# v1.net
KiCad netlist of a schematic drawn in EAGLE
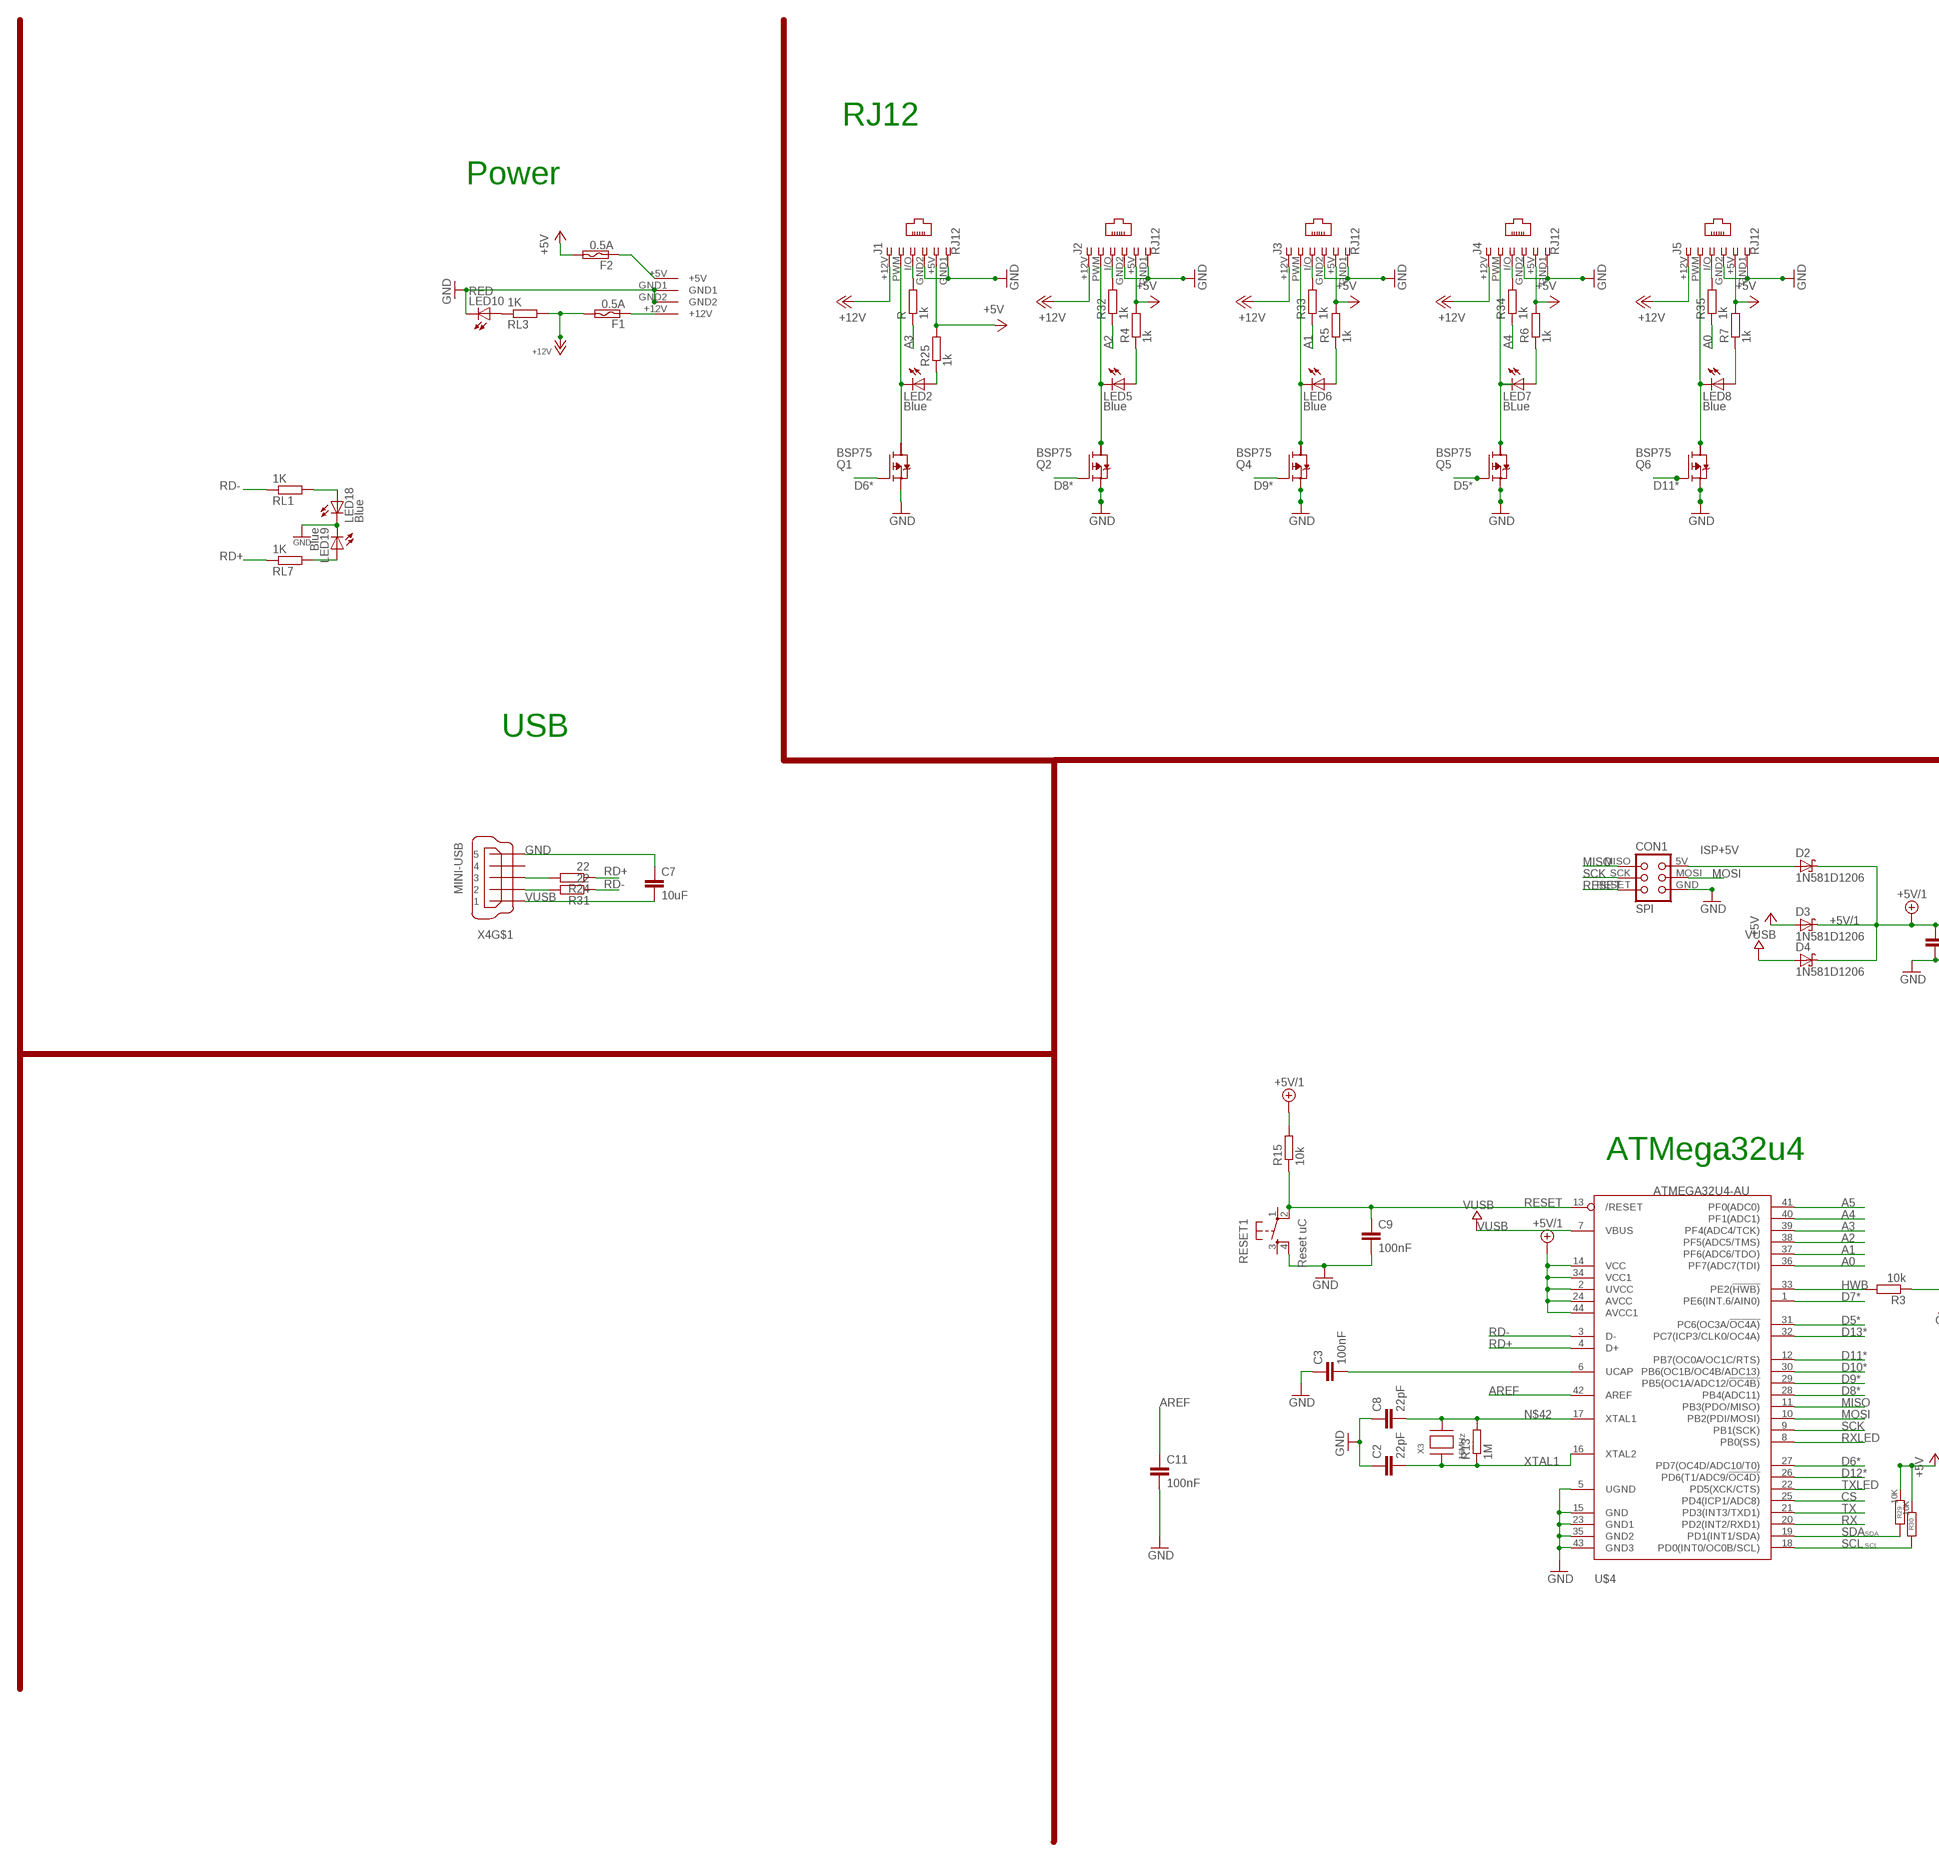
[diagram p0: schematic, sheet 1, part 1 of 2]
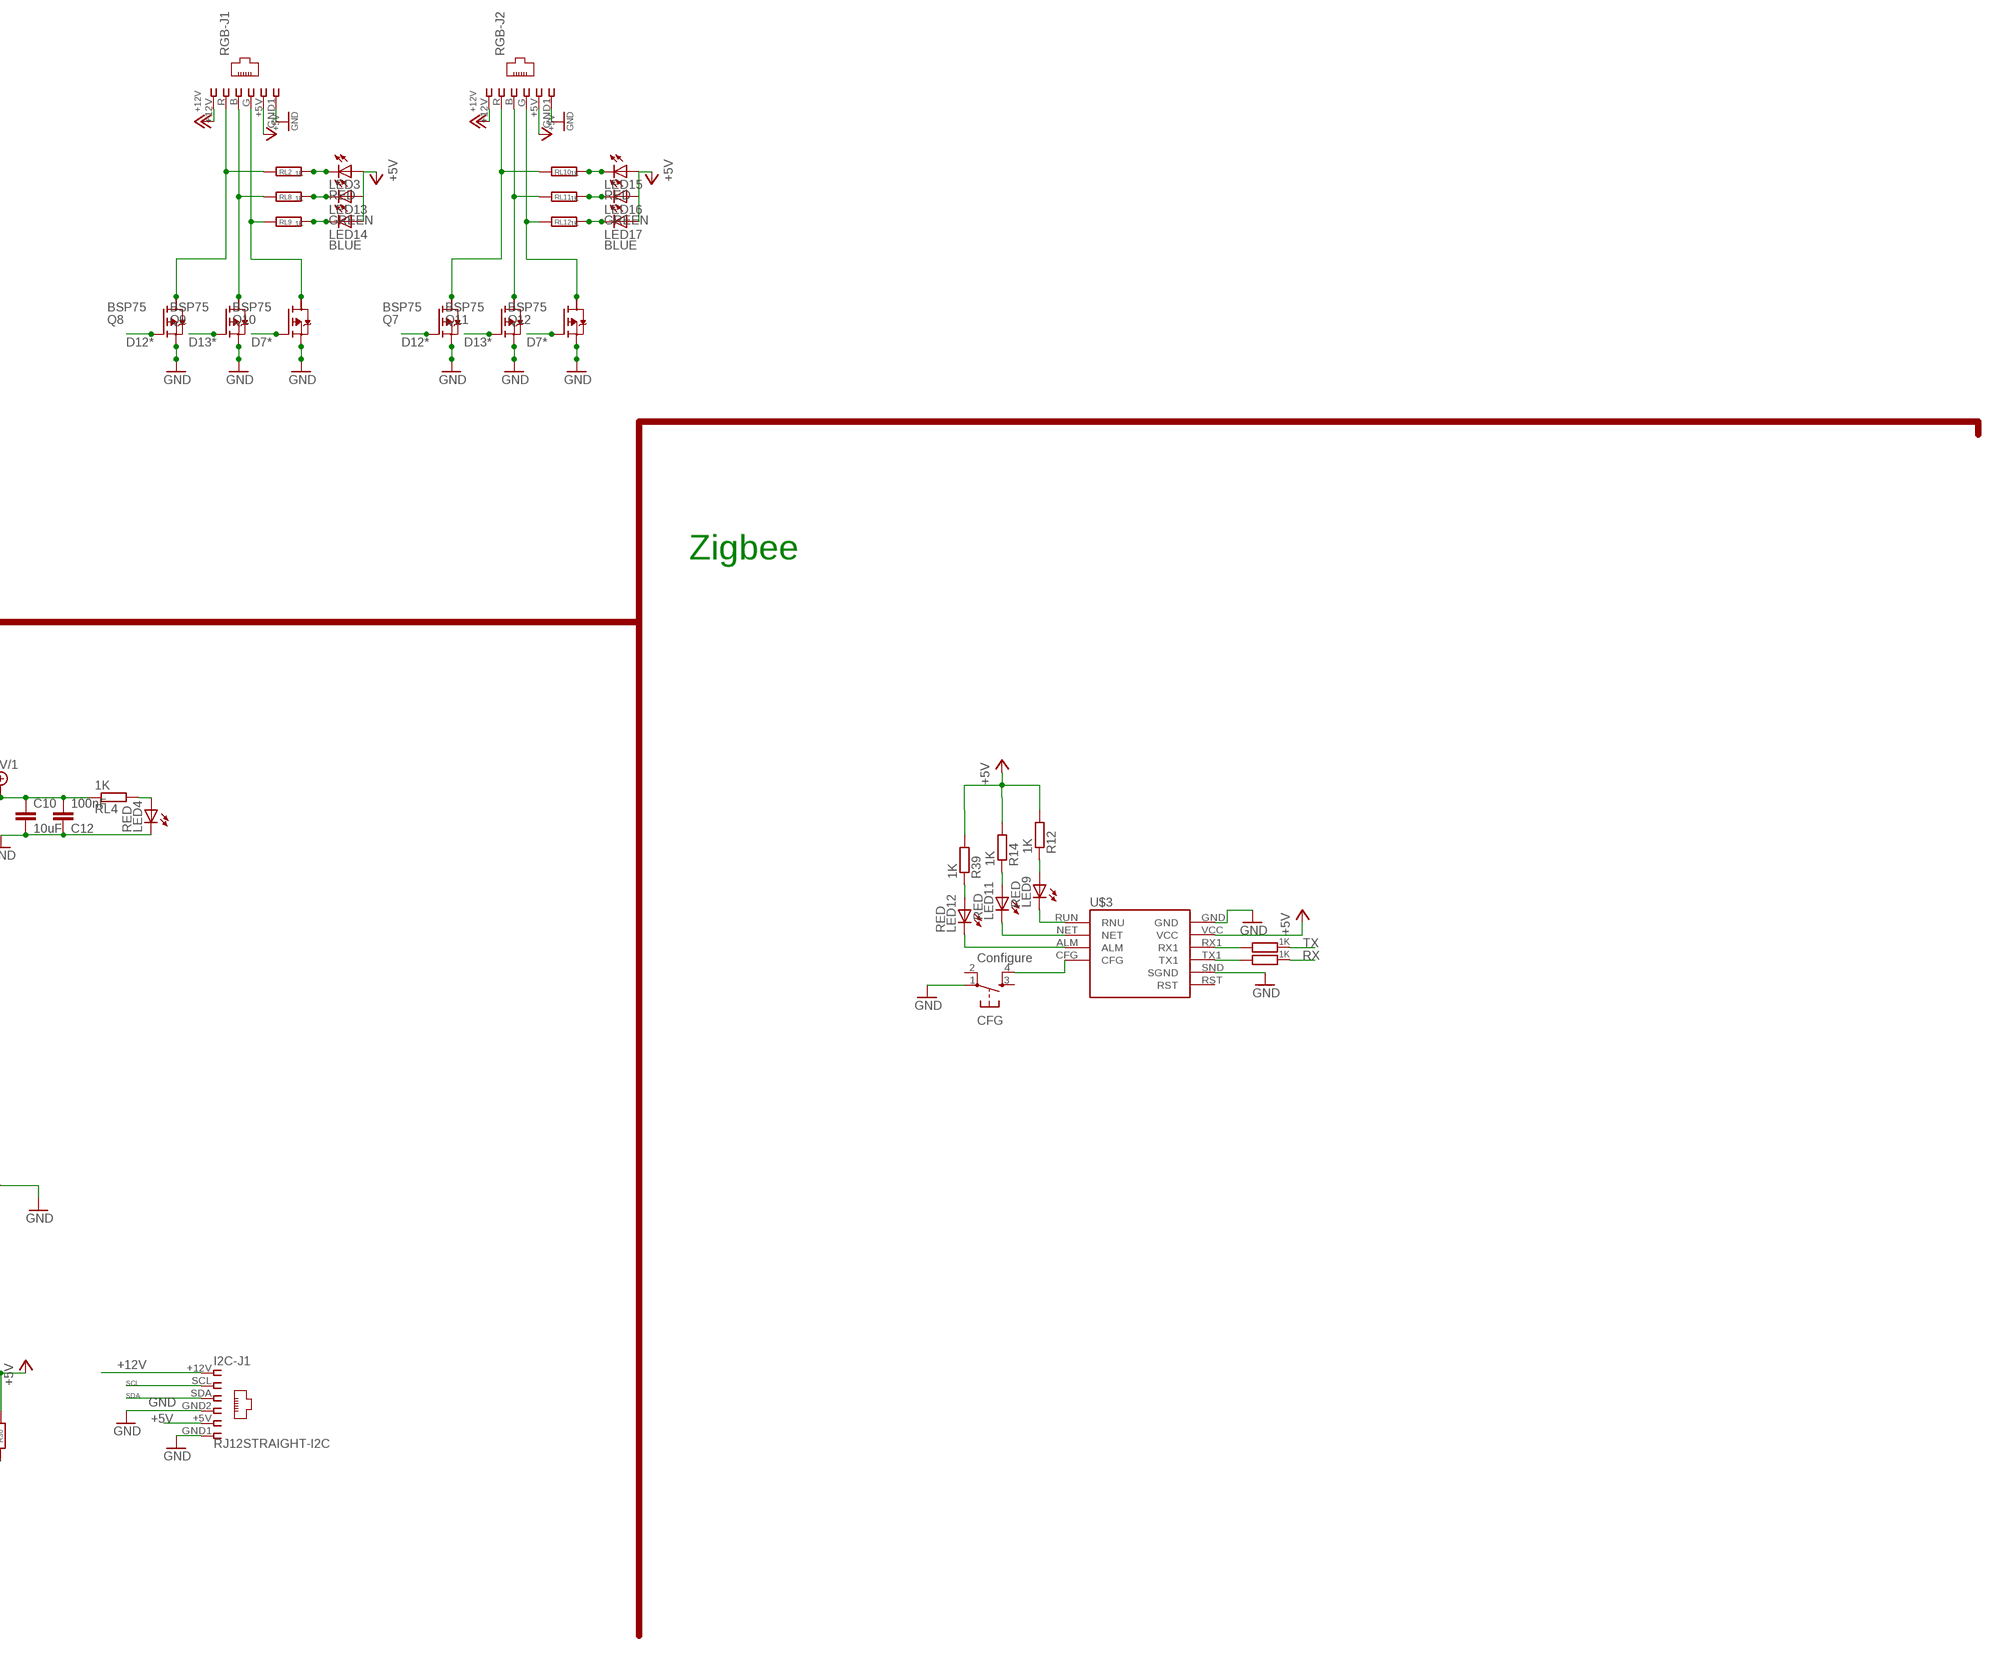
[diagram p1: schematic, sheet 1, part 2 of 2]

(export (version "E")
  (design (tool "Eeschema 10.0.6"))
  (components
    (comp (ref "C2")
      (value "22pF")
      (footprint "eagle-import:C1206")
      (libsource (lib "eagle-import") (part "C-EUC1206"))
    )
    (comp (ref "C3")
      (value "100nF")
      (footprint "eagle-import:C1206")
      (libsource (lib "eagle-import") (part "C-EUC1206"))
    )
    (comp (ref "C7")
      (value "10uF")
      (footprint "eagle-import:C1206")
      (libsource (lib "eagle-import") (part "C-EUC1206"))
    )
    (comp (ref "C8")
      (value "22pF")
      (footprint "eagle-import:C1206")
      (libsource (lib "eagle-import") (part "C-EUC1206"))
    )
    (comp (ref "C9")
      (value "100nF")
      (footprint "eagle-import:C1206")
      (libsource (lib "eagle-import") (part "C-EUC1206"))
    )
    (comp (ref "C10")
      (value "10uF")
      (footprint "eagle-import:C1206")
      (libsource (lib "eagle-import") (part "C-EUC1206"))
    )
    (comp (ref "C11")
      (value "100nF")
      (footprint "eagle-import:C1206")
      (libsource (lib "eagle-import") (part "C-EUC1206"))
    )
    (comp (ref "C12")
      (value "100nF")
      (footprint "eagle-import:C1206")
      (libsource (lib "eagle-import") (part "C-EUC1206"))
    )
    (comp (ref "CFG")
      (value "Configure")
      (footprint "eagle-import:TACTILE_SWITCH_SMD")
      (libsource (lib "eagle-import") (part "TAC_SWITCHSMD"))
    )
    (comp (ref "CON1")
      (value "SPI")
      (footprint "eagle-import:TC2030-MCP-NL")
      (libsource (lib "eagle-import") (part "TINYISPT"))
    )
    (comp (ref "D2")
      (value "1N581D1206")
      (footprint "eagle-import:LED-1206")
      (libsource (lib "eagle-import") (part "1N581D1206"))
    )
    (comp (ref "D3")
      (value "1N581D1206")
      (footprint "eagle-import:LED-1206")
      (libsource (lib "eagle-import") (part "1N581D1206"))
    )
    (comp (ref "D4")
      (value "1N581D1206")
      (footprint "eagle-import:LED-1206")
      (libsource (lib "eagle-import") (part "1N581D1206"))
    )
    (comp (ref "F1")
      (value "0.5A")
      (footprint "eagle-import:C1812")
      (libsource (lib "eagle-import") (part "POLYSWITCHSMD1812"))
    )
    (comp (ref "F2")
      (value "0.5A")
      (footprint "eagle-import:C1812")
      (libsource (lib "eagle-import") (part "POLYSWITCHSMD1812"))
    )
    (comp (ref "I2C-J1")
      (value "RJ12STRAIGHT-I2C")
      (footprint "eagle-import:RJ12-STRAIGHT-I2C")
      (libsource (lib "eagle-import") (part "RJ12STRAIGHT-I2C"))
    )
    (comp (ref "J1")
      (value "RJ12")
      (footprint "eagle-import:RJ12-STRAIGHT")
      (libsource (lib "eagle-import") (part "RJ12STRAIGHT"))
    )
    (comp (ref "J2")
      (value "RJ12")
      (footprint "eagle-import:RJ12-STRAIGHT")
      (libsource (lib "eagle-import") (part "RJ12STRAIGHT"))
    )
    (comp (ref "J3")
      (value "RJ12")
      (footprint "eagle-import:RJ12-STRAIGHT")
      (libsource (lib "eagle-import") (part "RJ12STRAIGHT"))
    )
    (comp (ref "J4")
      (value "RJ12")
      (footprint "eagle-import:RJ12-STRAIGHT")
      (libsource (lib "eagle-import") (part "RJ12STRAIGHT"))
    )
    (comp (ref "J5")
      (value "RJ12")
      (footprint "eagle-import:RJ12-STRAIGHT")
      (libsource (lib "eagle-import") (part "RJ12STRAIGHT"))
    )
    (comp (ref "LED2")
      (value "Blue")
      (footprint "eagle-import:CHIPLED_1206")
      (libsource (lib "eagle-import") (part "LEDCHIPLED_1206"))
    )
    (comp (ref "LED3")
      (value "RED")
      (footprint "eagle-import:CHIPLED_1206")
      (libsource (lib "eagle-import") (part "LEDCHIPLED_1206"))
    )
    (comp (ref "LED4")
      (value "RED")
      (footprint "eagle-import:CHIPLED_1206")
      (libsource (lib "eagle-import") (part "LEDCHIPLED_1206"))
    )
    (comp (ref "LED5")
      (value "Blue")
      (footprint "eagle-import:CHIPLED_1206")
      (libsource (lib "eagle-import") (part "LEDCHIPLED_1206"))
    )
    (comp (ref "LED6")
      (value "Blue")
      (footprint "eagle-import:CHIPLED_1206")
      (libsource (lib "eagle-import") (part "LEDCHIPLED_1206"))
    )
    (comp (ref "LED7")
      (value "BLue")
      (footprint "eagle-import:CHIPLED_1206")
      (libsource (lib "eagle-import") (part "LEDCHIPLED_1206"))
    )
    (comp (ref "LED8")
      (value "Blue")
      (footprint "eagle-import:CHIPLED_1206")
      (libsource (lib "eagle-import") (part "LEDCHIPLED_1206"))
    )
    (comp (ref "LED9")
      (value "RED")
      (footprint "eagle-import:CHIP-LED0805")
      (libsource (lib "eagle-import") (part "LEDCHIP-LED0805"))
    )
    (comp (ref "LED10")
      (value "RED")
      (footprint "eagle-import:CHIPLED_1206")
      (libsource (lib "eagle-import") (part "LEDCHIPLED_1206"))
    )
    (comp (ref "LED11")
      (value "RED")
      (footprint "eagle-import:CHIP-LED0805")
      (libsource (lib "eagle-import") (part "LEDCHIP-LED0805"))
    )
    (comp (ref "LED12")
      (value "RED")
      (footprint "eagle-import:CHIP-LED0805")
      (libsource (lib "eagle-import") (part "LEDCHIP-LED0805"))
    )
    (comp (ref "LED13")
      (value "GREEN")
      (footprint "eagle-import:CHIPLED_1206")
      (libsource (lib "eagle-import") (part "LEDCHIPLED_1206"))
    )
    (comp (ref "LED14")
      (value "BLUE")
      (footprint "eagle-import:CHIPLED_1206")
      (libsource (lib "eagle-import") (part "LEDCHIPLED_1206"))
    )
    (comp (ref "LED15")
      (value "RED")
      (footprint "eagle-import:CHIPLED_1206")
      (libsource (lib "eagle-import") (part "LEDCHIPLED_1206"))
    )
    (comp (ref "LED16")
      (value "GREEN")
      (footprint "eagle-import:CHIPLED_1206")
      (libsource (lib "eagle-import") (part "LEDCHIPLED_1206"))
    )
    (comp (ref "LED17")
      (value "BLUE")
      (footprint "eagle-import:CHIPLED_1206")
      (libsource (lib "eagle-import") (part "LEDCHIPLED_1206"))
    )
    (comp (ref "LED18")
      (value "Blue")
      (footprint "eagle-import:CHIPLED_1206")
      (libsource (lib "eagle-import") (part "LEDCHIPLED_1206"))
    )
    (comp (ref "LED19")
      (value "Blue")
      (footprint "eagle-import:CHIPLED_1206")
      (libsource (lib "eagle-import") (part "LEDCHIPLED_1206"))
    )
    (comp (ref "Q1")
      (value "BSP75")
      (footprint "eagle-import:PG-SOT-223")
      (libsource (lib "eagle-import") (part "BSP613P"))
    )
    (comp (ref "Q2")
      (value "BSP75")
      (footprint "eagle-import:PG-SOT-223")
      (libsource (lib "eagle-import") (part "BSP613P"))
    )
    (comp (ref "Q4")
      (value "BSP75")
      (footprint "eagle-import:PG-SOT-223")
      (libsource (lib "eagle-import") (part "BSP613P"))
    )
    (comp (ref "Q5")
      (value "BSP75")
      (footprint "eagle-import:PG-SOT-223")
      (libsource (lib "eagle-import") (part "BSP613P"))
    )
    (comp (ref "Q6")
      (value "BSP75")
      (footprint "eagle-import:PG-SOT-223")
      (libsource (lib "eagle-import") (part "BSP613P"))
    )
    (comp (ref "Q7")
      (value "BSP75")
      (footprint "eagle-import:PG-SOT-223")
      (libsource (lib "eagle-import") (part "BSP613P"))
    )
    (comp (ref "Q8")
      (value "BSP75")
      (footprint "eagle-import:PG-SOT-223")
      (libsource (lib "eagle-import") (part "BSP613P"))
    )
    (comp (ref "Q9")
      (value "BSP75")
      (footprint "eagle-import:PG-SOT-223")
      (libsource (lib "eagle-import") (part "BSP613P"))
    )
    (comp (ref "Q10")
      (value "BSP75")
      (footprint "eagle-import:PG-SOT-223")
      (libsource (lib "eagle-import") (part "BSP613P"))
    )
    (comp (ref "Q11")
      (value "BSP75")
      (footprint "eagle-import:PG-SOT-223")
      (libsource (lib "eagle-import") (part "BSP613P"))
    )
    (comp (ref "Q12")
      (value "BSP75")
      (footprint "eagle-import:PG-SOT-223")
      (libsource (lib "eagle-import") (part "BSP613P"))
    )
    (comp (ref "R")
      (value "1k")
      (footprint "eagle-import:R0805")
      (libsource (lib "eagle-import") (part "R-EU_R0805"))
    )
    (comp (ref "R3")
      (value "10k")
      (footprint "eagle-import:M0805")
      (libsource (lib "eagle-import") (part "resistor_R-EU_M0805"))
    )
    (comp (ref "R4")
      (value "1k")
      (footprint "eagle-import:R0805")
      (libsource (lib "eagle-import") (part "R-EU_R0805"))
    )
    (comp (ref "R5")
      (value "1k")
      (footprint "eagle-import:R0805")
      (libsource (lib "eagle-import") (part "R-EU_R0805"))
    )
    (comp (ref "R6")
      (value "1k")
      (footprint "eagle-import:R0805")
      (libsource (lib "eagle-import") (part "R-EU_R0805"))
    )
    (comp (ref "R7")
      (value "1k")
      (footprint "eagle-import:R0805")
      (libsource (lib "eagle-import") (part "R-EU_R0805"))
    )
    (comp (ref "R8")
      (value "1K")
      (footprint "eagle-import:R0805")
      (libsource (lib "eagle-import") (part "R-EU_R0805"))
    )
    (comp (ref "R11")
      (value "1K")
      (footprint "eagle-import:R0805")
      (libsource (lib "eagle-import") (part "R-EU_R0805"))
    )
    (comp (ref "R12")
      (value "1K")
      (footprint "eagle-import:R0805")
      (libsource (lib "eagle-import") (part "R-EU_R0805"))
    )
    (comp (ref "R13")
      (value "1M")
      (footprint "eagle-import:R1206")
      (libsource (lib "eagle-import") (part "R-EU_R1206"))
    )
    (comp (ref "R14")
      (value "1K")
      (footprint "eagle-import:R0805")
      (libsource (lib "eagle-import") (part "R-EU_R0805"))
    )
    (comp (ref "R15")
      (value "10k")
      (footprint "eagle-import:M0805")
      (libsource (lib "eagle-import") (part "resistor_R-EU_M0805"))
    )
    (comp (ref "R24")
      (value "22")
      (footprint "eagle-import:M1206")
      (libsource (lib "eagle-import") (part "resistor_R-EU_M1206"))
    )
    (comp (ref "R25")
      (value "1k")
      (footprint "eagle-import:R0805")
      (libsource (lib "eagle-import") (part "R-EU_R0805"))
    )
    (comp (ref "R29")
      (value "10K")
      (footprint "eagle-import:M0805")
      (libsource (lib "eagle-import") (part "resistor_R-EU_M0805"))
    )
    (comp (ref "R30")
      (value "10K")
      (footprint "eagle-import:M0805")
      (libsource (lib "eagle-import") (part "resistor_R-EU_M0805"))
    )
    (comp (ref "R31")
      (value "22")
      (footprint "eagle-import:M1206")
      (libsource (lib "eagle-import") (part "resistor_R-EU_M1206"))
    )
    (comp (ref "R32")
      (value "1k")
      (footprint "eagle-import:R0805")
      (libsource (lib "eagle-import") (part "R-EU_R0805"))
    )
    (comp (ref "R33")
      (value "1k")
      (footprint "eagle-import:R0805")
      (libsource (lib "eagle-import") (part "R-EU_R0805"))
    )
    (comp (ref "R34")
      (value "1k")
      (footprint "eagle-import:R0805")
      (libsource (lib "eagle-import") (part "R-EU_R0805"))
    )
    (comp (ref "R35")
      (value "1k")
      (footprint "eagle-import:R0805")
      (libsource (lib "eagle-import") (part "R-EU_R0805"))
    )
    (comp (ref "R39")
      (value "1K")
      (footprint "eagle-import:R0805")
      (libsource (lib "eagle-import") (part "R-EU_R0805"))
    )
    (comp (ref "RESET1")
      (value "Reset uC")
      (footprint "eagle-import:TACTILE_SWITCH_SMD")
      (libsource (lib "eagle-import") (part "TAC_SWITCHSMD"))
    )
    (comp (ref "RGB-J1")
      (value "RJ12")
      (footprint "eagle-import:RJ12-STRAIGHT-RGB")
      (libsource (lib "eagle-import") (part "RJ12STRAIGHT-RGB"))
    )
    (comp (ref "RGB-J2")
      (value "RJ12")
      (footprint "eagle-import:RJ12-STRAIGHT-RGB")
      (libsource (lib "eagle-import") (part "RJ12STRAIGHT-RGB"))
    )
    (comp (ref "RL1")
      (value "1K")
      (footprint "eagle-import:R0805")
      (libsource (lib "eagle-import") (part "R-EU_R0805"))
    )
    (comp (ref "RL2")
      (value "1K")
      (footprint "eagle-import:M0805")
      (libsource (lib "eagle-import") (part "resistor_R-EU_M0805"))
    )
    (comp (ref "RL3")
      (value "1K")
      (footprint "eagle-import:R0805")
      (libsource (lib "eagle-import") (part "R-EU_R0805"))
    )
    (comp (ref "RL4")
      (value "1K")
      (footprint "eagle-import:R0805")
      (libsource (lib "eagle-import") (part "resistor_R-EU_R0805"))
    )
    (comp (ref "RL7")
      (value "1K")
      (footprint "eagle-import:R0805")
      (libsource (lib "eagle-import") (part "R-EU_R0805"))
    )
    (comp (ref "RL8")
      (value "1K")
      (footprint "eagle-import:M0805")
      (libsource (lib "eagle-import") (part "resistor_R-EU_M0805"))
    )
    (comp (ref "RL9")
      (value "1K")
      (footprint "eagle-import:M0805")
      (libsource (lib "eagle-import") (part "resistor_R-EU_M0805"))
    )
    (comp (ref "RL10")
      (value "1K")
      (footprint "eagle-import:M0805")
      (libsource (lib "eagle-import") (part "resistor_R-EU_M0805"))
    )
    (comp (ref "RL11")
      (value "1K")
      (footprint "eagle-import:M0805")
      (libsource (lib "eagle-import") (part "resistor_R-EU_M0805"))
    )
    (comp (ref "RL12")
      (value "1K")
      (footprint "eagle-import:M0805")
      (libsource (lib "eagle-import") (part "resistor_R-EU_M0805"))
    )
    (comp (ref "U$3")
      (value "SZ05-ZIGBEESMD")
      (footprint "eagle-import:SZ05-ZIGBEE3")
      (libsource (lib "eagle-import") (part "SZ05-ZIGBEESMD"))
    )
    (comp (ref "U$4")
      (value "ATMEGA32U4-AU")
      (footprint "eagle-import:TQFP44")
      (libsource (lib "eagle-import") (part "ATMEGA32U4-AU"))
    )
    (comp (ref "U$6")
      (value "KPJX-4S-S")
      (footprint "eagle-import:KPJX-4S-S")
      (libsource (lib "eagle-import") (part "KPJX-4S-S"))
    )
    (comp (ref "X3")
      (value "16MHz")
      (footprint "eagle-import:NX6035")
      (libsource (lib "eagle-import") (part "XTALNX6035"))
    )
    (comp (ref "X4")
      (value "MINI-USB")
      (footprint "eagle-import:32005-201")
      (libsource (lib "eagle-import") (part "MINI-USB-SCHIELD-32005-201"))
    )
  )
  (nets
    (net (code "1") (name "+5V") (class "Default")
      (node (ref "D3") (pin "A") (pinfunction "A_A") (pintype "passive"))
      (node (ref "F2") (pin "2") (pinfunction "2_2") (pintype "passive"))
      (node (ref "I2C-J1") (pin "+5V") (pinfunction "5_+5V") (pintype "bidirectional"))
      (node (ref "J1") (pin "+5V") (pinfunction "5_+5V") (pintype "bidirectional"))
      (node (ref "J2") (pin "+5V") (pinfunction "5_+5V") (pintype "bidirectional"))
      (node (ref "J3") (pin "+5V") (pinfunction "5_+5V") (pintype "bidirectional"))
      (node (ref "J4") (pin "+5V") (pinfunction "5_+5V") (pintype "bidirectional"))
      (node (ref "J5") (pin "+5V") (pinfunction "5_+5V") (pintype "bidirectional"))
      (node (ref "LED13") (pin "A") (pinfunction "A_A") (pintype "passive"))
      (node (ref "LED14") (pin "A") (pinfunction "A_A") (pintype "passive"))
      (node (ref "LED15") (pin "A") (pinfunction "A_A") (pintype "passive"))
      (node (ref "LED16") (pin "A") (pinfunction "A_A") (pintype "passive"))
      (node (ref "LED17") (pin "A") (pinfunction "A_A") (pintype "passive"))
      (node (ref "LED3") (pin "A") (pinfunction "A_A") (pintype "passive"))
      (node (ref "R12") (pin "2") (pinfunction "2_2") (pintype "passive"))
      (node (ref "R14") (pin "2") (pinfunction "2_2") (pintype "passive"))
      (node (ref "R25") (pin "2") (pinfunction "2_2") (pintype "passive"))
      (node (ref "R29") (pin "1") (pinfunction "1_1") (pintype "passive"))
      (node (ref "R30") (pin "1") (pinfunction "1_1") (pintype "passive"))
      (node (ref "R39") (pin "2") (pinfunction "2_2") (pintype "passive"))
      (node (ref "R4") (pin "2") (pinfunction "2_2") (pintype "passive"))
      (node (ref "R5") (pin "2") (pinfunction "2_2") (pintype "passive"))
      (node (ref "R6") (pin "2") (pinfunction "2_2") (pintype "passive"))
      (node (ref "R7") (pin "2") (pinfunction "2_2") (pintype "passive"))
      (node (ref "RGB-J1") (pin "+5V") (pinfunction "5_+5V") (pintype "bidirectional"))
      (node (ref "RGB-J2") (pin "+5V") (pinfunction "5_+5V") (pintype "bidirectional"))
      (node (ref "U$3") (pin "VCC") (pinfunction "VCC_VCC") (pintype "bidirectional"))
    )
    (net (code "2") (name "+5V{slash}1") (class "Default")
      (node (ref "C10") (pin "1") (pinfunction "1_1") (pintype "passive"))
      (node (ref "C12") (pin "2") (pinfunction "2_2") (pintype "passive"))
      (node (ref "D2") (pin "C") (pinfunction "C_C") (pintype "passive"))
      (node (ref "D3") (pin "C") (pinfunction "C_C") (pintype "passive"))
      (node (ref "D4") (pin "C") (pinfunction "C_C") (pintype "passive"))
      (node (ref "R15") (pin "2") (pinfunction "2_2") (pintype "passive"))
      (node (ref "RL4") (pin "1") (pinfunction "1_1") (pintype "passive"))
      (node (ref "U$4") (pin "14") (pinfunction "VCC_14") (pintype "bidirectional"))
      (node (ref "U$4") (pin "2") (pinfunction "UVCC_2") (pintype "bidirectional"))
      (node (ref "U$4") (pin "24") (pinfunction "AVCC_24") (pintype "bidirectional"))
      (node (ref "U$4") (pin "34") (pinfunction "VCC1_34") (pintype "bidirectional"))
      (node (ref "U$4") (pin "44") (pinfunction "AVCC1_44") (pintype "bidirectional"))
    )
    (net (code "3") (name "+12V") (class "Default")
      (node (ref "F1") (pin "2") (pinfunction "2_2") (pintype "passive"))
      (node (ref "I2C-J1") (pin "+12V") (pinfunction "1_+12V") (pintype "bidirectional"))
      (node (ref "J1") (pin "+12V") (pinfunction "1_+12V") (pintype "bidirectional"))
      (node (ref "J2") (pin "+12V") (pinfunction "1_+12V") (pintype "bidirectional"))
      (node (ref "J3") (pin "+12V") (pinfunction "1_+12V") (pintype "bidirectional"))
      (node (ref "J4") (pin "+12V") (pinfunction "1_+12V") (pintype "bidirectional"))
      (node (ref "J5") (pin "+12V") (pinfunction "1_+12V") (pintype "bidirectional"))
      (node (ref "RGB-J1") (pin "+12V") (pinfunction "1_+12V") (pintype "bidirectional"))
      (node (ref "RGB-J2") (pin "+12V") (pinfunction "1_+12V") (pintype "bidirectional"))
      (node (ref "RL3") (pin "2") (pinfunction "2_2") (pintype "passive"))
    )
    (net (code "4") (name "/A0") (class "Default")
      (node (ref "R35") (pin "1") (pinfunction "1_1") (pintype "passive"))
      (node (ref "U$4") (pin "36") (pinfunction "PF7(ADC7(TDI)_36") (pintype "bidirectional"))
    )
    (net (code "5") (name "/A1") (class "Default")
      (node (ref "R33") (pin "1") (pinfunction "1_1") (pintype "passive"))
      (node (ref "U$4") (pin "37") (pinfunction "PF6(ADC6/TDO)_37") (pintype "bidirectional"))
    )
    (net (code "6") (name "/A2") (class "Default")
      (node (ref "R32") (pin "1") (pinfunction "1_1") (pintype "passive"))
      (node (ref "U$4") (pin "38") (pinfunction "PF5(ADC5/TMS)_38") (pintype "bidirectional"))
    )
    (net (code "7") (name "/A3") (class "Default")
      (node (ref "R") (pin "1") (pinfunction "1_1") (pintype "passive"))
      (node (ref "U$4") (pin "39") (pinfunction "PF4(ADC4/TCK)_39") (pintype "bidirectional"))
    )
    (net (code "8") (name "/A4") (class "Default")
      (node (ref "R34") (pin "1") (pinfunction "1_1") (pintype "passive"))
      (node (ref "U$4") (pin "40") (pinfunction "PF1(ADC1)_40") (pintype "bidirectional"))
    )
    (net (code "9") (name "/A5") (class "Default")
      (node (ref "U$4") (pin "41") (pinfunction "PF0(ADC0)_41") (pintype "bidirectional"))
    )
    (net (code "10") (name "/AREF") (class "Default")
      (node (ref "C11") (pin "1") (pinfunction "1_1") (pintype "passive"))
      (node (ref "U$4") (pin "42") (pinfunction "AREF_42") (pintype "bidirectional"))
    )
    (net (code "11") (name "/CS") (class "Default")
      (node (ref "U$4") (pin "25") (pinfunction "PD4(ICP1/ADC8)_25") (pintype "bidirectional"))
    )
    (net (code "12") (name "/D5*") (class "Default")
      (node (ref "Q5") (pin "1") (pinfunction "G_1") (pintype "passive"))
      (node (ref "U$4") (pin "31") (pinfunction "PC6(OC3A/~{OC4A})_31") (pintype "bidirectional"))
    )
    (net (code "13") (name "/D6*") (class "Default")
      (node (ref "Q1") (pin "1") (pinfunction "G_1") (pintype "passive"))
      (node (ref "U$4") (pin "27") (pinfunction "PD7(OC4D/ADC10/T0)_27") (pintype "bidirectional"))
    )
    (net (code "14") (name "/D7*") (class "Default")
      (node (ref "Q10") (pin "1") (pinfunction "G_1") (pintype "passive"))
      (node (ref "Q12") (pin "1") (pinfunction "G_1") (pintype "passive"))
      (node (ref "U$4") (pin "1") (pinfunction "PE6(INT.6/AIN0)_1") (pintype "bidirectional"))
    )
    (net (code "15") (name "/D8*") (class "Default")
      (node (ref "Q2") (pin "1") (pinfunction "G_1") (pintype "passive"))
      (node (ref "U$4") (pin "28") (pinfunction "PB4(ADC11)_28") (pintype "bidirectional"))
    )
    (net (code "16") (name "/D9*") (class "Default")
      (node (ref "Q4") (pin "1") (pinfunction "G_1") (pintype "passive"))
      (node (ref "U$4") (pin "29") (pinfunction "PB5(OC1A/ADC12/~{OC4B})_29") (pintype "bidirectional"))
    )
    (net (code "17") (name "/D10*") (class "Default")
      (node (ref "U$4") (pin "30") (pinfunction "PB6(OC1B/OC4B/ADC13)_30") (pintype "bidirectional"))
    )
    (net (code "18") (name "/D11*") (class "Default")
      (node (ref "Q6") (pin "1") (pinfunction "G_1") (pintype "passive"))
      (node (ref "U$4") (pin "12") (pinfunction "PB7(OC0A/OC1C/RTS)_12") (pintype "bidirectional"))
    )
    (net (code "19") (name "/D12*") (class "Default")
      (node (ref "Q7") (pin "1") (pinfunction "G_1") (pintype "passive"))
      (node (ref "Q8") (pin "1") (pinfunction "G_1") (pintype "passive"))
      (node (ref "U$4") (pin "26") (pinfunction "PD6(T1/ADC9/~{OC4D})_26") (pintype "bidirectional"))
    )
    (net (code "20") (name "/D13*") (class "Default")
      (node (ref "Q11") (pin "1") (pinfunction "G_1") (pintype "passive"))
      (node (ref "Q9") (pin "1") (pinfunction "G_1") (pintype "passive"))
      (node (ref "U$4") (pin "32") (pinfunction "PC7(ICP3/CLK0/OC4A)_32") (pintype "bidirectional"))
    )
    (net (code "21") (name "/HWB") (class "Default")
      (node (ref "R3") (pin "2") (pinfunction "2_2") (pintype "passive"))
      (node (ref "U$4") (pin "33") (pinfunction "PE2(~{HWB})_33") (pintype "bidirectional"))
    )
    (net (code "22") (name "/ISP+5V") (class "Default")
      (node (ref "CON1") (pin "5V") (pinfunction "VCC_5V") (pintype "passive"))
      (node (ref "D2") (pin "A") (pinfunction "A_A") (pintype "passive"))
    )
    (net (code "23") (name "/MISO") (class "Default")
      (node (ref "CON1") (pin "MISO") (pinfunction "MISO_MISO") (pintype "passive"))
      (node (ref "U$4") (pin "11") (pinfunction "PB3(PDO/MISO)_11") (pintype "bidirectional"))
    )
    (net (code "24") (name "/MOSI") (class "Default")
      (node (ref "CON1") (pin "MOSI") (pinfunction "MOSI_MOSI") (pintype "passive"))
      (node (ref "U$4") (pin "10") (pinfunction "PB2(PDI/MOSI)_10") (pintype "bidirectional"))
    )
    (net (code "25") (name "/N$42") (class "Default")
      (node (ref "C8") (pin "2") (pinfunction "2_2") (pintype "passive"))
      (node (ref "R13") (pin "2") (pinfunction "2_2") (pintype "passive"))
      (node (ref "U$4") (pin "17") (pinfunction "XTAL1_17") (pintype "bidirectional"))
      (node (ref "X3") (pin "P$2") (pinfunction "P$2_P$2") (pintype "bidirectional"))
    )
    (net (code "26") (name "/RD+") (class "Default")
      (node (ref "R24") (pin "1") (pinfunction "1_1") (pintype "passive"))
      (node (ref "RL7") (pin "1") (pinfunction "1_1") (pintype "passive"))
      (node (ref "U$4") (pin "4") (pinfunction "D+_4") (pintype "bidirectional"))
    )
    (net (code "27") (name "/RD-") (class "Default")
      (node (ref "R31") (pin "1") (pinfunction "1_1") (pintype "passive"))
      (node (ref "RL1") (pin "1") (pinfunction "1_1") (pintype "passive"))
      (node (ref "U$4") (pin "3") (pinfunction "D-_3") (pintype "bidirectional"))
    )
    (net (code "28") (name "/RESET") (class "Default")
      (node (ref "C9") (pin "1") (pinfunction "1_1") (pintype "passive"))
      (node (ref "CON1") (pin "RESET") (pinfunction "RESET_RESET") (pintype "passive"))
      (node (ref "R15") (pin "1") (pinfunction "1_1") (pintype "passive"))
      (node (ref "RESET1") (pin "2") (pinfunction "2_2") (pintype "passive"))
      (node (ref "U$4") (pin "13") (pinfunction "/RESET_13") (pintype "bidirectional"))
    )
    (net (code "29") (name "/RX") (class "Default")
      (node (ref "R8") (pin "1") (pinfunction "1_1") (pintype "passive"))
      (node (ref "U$4") (pin "20") (pinfunction "PD2(INT2/RXD1)_20") (pintype "bidirectional"))
    )
    (net (code "30") (name "/RXLED") (class "Default")
      (node (ref "U$4") (pin "8") (pinfunction "PB0(SS)_8") (pintype "bidirectional"))
    )
    (net (code "31") (name "/SCK") (class "Default")
      (node (ref "CON1") (pin "SCK") (pinfunction "SCK_SCK") (pintype "passive"))
      (node (ref "U$4") (pin "9") (pinfunction "PB1(SCK)_9") (pintype "bidirectional"))
    )
    (net (code "32") (name "/SCL") (class "Default")
      (node (ref "I2C-J1") (pin "SCL") (pinfunction "2_SCL") (pintype "bidirectional"))
      (node (ref "R30") (pin "2") (pinfunction "2_2") (pintype "passive"))
      (node (ref "U$4") (pin "18") (pinfunction "PD0(INT0/OC0B/SCL)_18") (pintype "bidirectional"))
    )
    (net (code "33") (name "/SDA") (class "Default")
      (node (ref "I2C-J1") (pin "SDA") (pinfunction "3_SDA") (pintype "bidirectional"))
      (node (ref "R29") (pin "2") (pinfunction "2_2") (pintype "passive"))
      (node (ref "U$4") (pin "19") (pinfunction "PD1(INT1/SDA)_19") (pintype "bidirectional"))
    )
    (net (code "34") (name "/TX") (class "Default")
      (node (ref "R11") (pin "1") (pinfunction "1_1") (pintype "passive"))
      (node (ref "U$4") (pin "21") (pinfunction "PD3(INT3/TXD1)_21") (pintype "bidirectional"))
    )
    (net (code "35") (name "/TXLED") (class "Default")
      (node (ref "U$4") (pin "22") (pinfunction "PD5(XCK/CTS)_22") (pintype "bidirectional"))
    )
    (net (code "36") (name "/XTAL1") (class "Default")
      (node (ref "C2") (pin "2") (pinfunction "2_2") (pintype "passive"))
      (node (ref "R13") (pin "1") (pinfunction "1_1") (pintype "passive"))
      (node (ref "U$4") (pin "16") (pinfunction "XTAL2_16") (pintype "bidirectional"))
      (node (ref "X3") (pin "P$1") (pinfunction "P$1_P$1") (pintype "bidirectional"))
    )
    (net (code "37") (name "GND") (class "Default")
      (node (ref "C10") (pin "2") (pinfunction "2_2") (pintype "passive"))
      (node (ref "C11") (pin "2") (pinfunction "2_2") (pintype "passive"))
      (node (ref "C12") (pin "1") (pinfunction "1_1") (pintype "passive"))
      (node (ref "C2") (pin "1") (pinfunction "1_1") (pintype "passive"))
      (node (ref "C3") (pin "1") (pinfunction "1_1") (pintype "passive"))
      (node (ref "C7") (pin "1") (pinfunction "1_1") (pintype "passive"))
      (node (ref "C8") (pin "1") (pinfunction "1_1") (pintype "passive"))
      (node (ref "C9") (pin "2") (pinfunction "2_2") (pintype "passive"))
      (node (ref "CFG") (pin "1") (pinfunction "1_1") (pintype "passive"))
      (node (ref "CON1") (pin "GND") (pinfunction "GND_GND") (pintype "passive"))
      (node (ref "I2C-J1") (pin "GND1") (pinfunction "6_GND1") (pintype "bidirectional"))
      (node (ref "I2C-J1") (pin "GND2") (pinfunction "4_GND2") (pintype "bidirectional"))
      (node (ref "J1") (pin "GND1") (pinfunction "6_GND1") (pintype "bidirectional"))
      (node (ref "J1") (pin "GND2") (pinfunction "4_GND2") (pintype "bidirectional"))
      (node (ref "J2") (pin "GND1") (pinfunction "6_GND1") (pintype "bidirectional"))
      (node (ref "J2") (pin "GND2") (pinfunction "4_GND2") (pintype "bidirectional"))
      (node (ref "J3") (pin "GND1") (pinfunction "6_GND1") (pintype "bidirectional"))
      (node (ref "J3") (pin "GND2") (pinfunction "4_GND2") (pintype "bidirectional"))
      (node (ref "J4") (pin "GND1") (pinfunction "6_GND1") (pintype "bidirectional"))
      (node (ref "J4") (pin "GND2") (pinfunction "4_GND2") (pintype "bidirectional"))
      (node (ref "J5") (pin "GND1") (pinfunction "6_GND1") (pintype "bidirectional"))
      (node (ref "J5") (pin "GND2") (pinfunction "4_GND2") (pintype "bidirectional"))
      (node (ref "LED10") (pin "C") (pinfunction "C_C") (pintype "passive"))
      (node (ref "LED18") (pin "C") (pinfunction "C_C") (pintype "passive"))
      (node (ref "LED19") (pin "C") (pinfunction "C_C") (pintype "passive"))
      (node (ref "LED4") (pin "C") (pinfunction "C_C") (pintype "passive"))
      (node (ref "Q1") (pin "3") (pinfunction "S_3") (pintype "passive"))
      (node (ref "Q10") (pin "3") (pinfunction "S_3") (pintype "passive"))
      (node (ref "Q11") (pin "3") (pinfunction "S_3") (pintype "passive"))
      (node (ref "Q12") (pin "3") (pinfunction "S_3") (pintype "passive"))
      (node (ref "Q2") (pin "3") (pinfunction "S_3") (pintype "passive"))
      (node (ref "Q4") (pin "3") (pinfunction "S_3") (pintype "passive"))
      (node (ref "Q5") (pin "3") (pinfunction "S_3") (pintype "passive"))
      (node (ref "Q6") (pin "3") (pinfunction "S_3") (pintype "passive"))
      (node (ref "Q7") (pin "3") (pinfunction "S_3") (pintype "passive"))
      (node (ref "Q8") (pin "3") (pinfunction "S_3") (pintype "passive"))
      (node (ref "Q9") (pin "3") (pinfunction "S_3") (pintype "passive"))
      (node (ref "R3") (pin "1") (pinfunction "1_1") (pintype "passive"))
      (node (ref "RESET1") (pin "4") (pinfunction "4_4") (pintype "passive"))
      (node (ref "RGB-J1") (pin "GND1") (pinfunction "6_GND1") (pintype "bidirectional"))
      (node (ref "RGB-J2") (pin "GND1") (pinfunction "6_GND1") (pintype "bidirectional"))
      (node (ref "U$3") (pin "GND") (pinfunction "GND_GND") (pintype "bidirectional"))
      (node (ref "U$3") (pin "SND") (pinfunction "SGND_SND") (pintype "bidirectional"))
      (node (ref "U$4") (pin "15") (pinfunction "GND_15") (pintype "bidirectional"))
      (node (ref "U$4") (pin "23") (pinfunction "GND1_23") (pintype "bidirectional"))
      (node (ref "U$4") (pin "35") (pinfunction "GND2_35") (pintype "bidirectional"))
      (node (ref "U$4") (pin "43") (pinfunction "GND3_43") (pintype "bidirectional"))
      (node (ref "U$4") (pin "5") (pinfunction "UGND_5") (pintype "bidirectional"))
      (node (ref "U$6") (pin "GND1") (pinfunction "GND1_GND1") (pintype "input"))
      (node (ref "U$6") (pin "GND2") (pinfunction "GND2_GND2") (pintype "input"))
      (node (ref "X4") (pin "5") (pinfunction "5_5") (pintype "passive"))
    )
    (net (code "38") (name "Net-(CFG-Pad4)") (class "Default")
      (node (ref "CFG") (pin "4") (pinfunction "4_4") (pintype "passive"))
      (node (ref "U$3") (pin "CFG") (pinfunction "CFG_CFG") (pintype "bidirectional"))
    )
    (net (code "39") (name "Net-(F1-Pad1)") (class "Default")
      (node (ref "F1") (pin "1") (pinfunction "1_1") (pintype "passive"))
      (node (ref "U$6") (pin "+12V") (pinfunction "+12V_+12V") (pintype "power_in"))
    )
    (net (code "40") (name "Net-(F2-Pad1)") (class "Default")
      (node (ref "F2") (pin "1") (pinfunction "1_1") (pintype "passive"))
      (node (ref "U$6") (pin "+5V") (pinfunction "+5V_+5V") (pintype "power_in"))
    )
    (net (code "41") (name "Net-(J1-2)") (class "Default")
      (node (ref "J1") (pin "PWM") (pinfunction "2_PWM") (pintype "bidirectional"))
      (node (ref "LED2") (pin "C") (pinfunction "C_C") (pintype "passive"))
      (node (ref "Q1") (pin "2") (pinfunction "D_2") (pintype "passive"))
    )
    (net (code "42") (name "Net-(J1-3)") (class "Default")
      (node (ref "J1") (pin "I/O") (pinfunction "3_I/O") (pintype "bidirectional"))
      (node (ref "R") (pin "2") (pinfunction "2_2") (pintype "passive"))
    )
    (net (code "43") (name "Net-(J2-2)") (class "Default")
      (node (ref "J2") (pin "PWM") (pinfunction "2_PWM") (pintype "bidirectional"))
      (node (ref "LED5") (pin "C") (pinfunction "C_C") (pintype "passive"))
      (node (ref "Q2") (pin "2") (pinfunction "D_2") (pintype "passive"))
    )
    (net (code "44") (name "Net-(J2-3)") (class "Default")
      (node (ref "J2") (pin "I/O") (pinfunction "3_I/O") (pintype "bidirectional"))
      (node (ref "R32") (pin "2") (pinfunction "2_2") (pintype "passive"))
    )
    (net (code "45") (name "Net-(J3-2)") (class "Default")
      (node (ref "J3") (pin "PWM") (pinfunction "2_PWM") (pintype "bidirectional"))
      (node (ref "LED6") (pin "C") (pinfunction "C_C") (pintype "passive"))
      (node (ref "Q4") (pin "2") (pinfunction "D_2") (pintype "passive"))
    )
    (net (code "46") (name "Net-(J3-3)") (class "Default")
      (node (ref "J3") (pin "I/O") (pinfunction "3_I/O") (pintype "bidirectional"))
      (node (ref "R33") (pin "2") (pinfunction "2_2") (pintype "passive"))
    )
    (net (code "47") (name "Net-(J4-2)") (class "Default")
      (node (ref "J4") (pin "PWM") (pinfunction "2_PWM") (pintype "bidirectional"))
      (node (ref "LED7") (pin "C") (pinfunction "C_C") (pintype "passive"))
      (node (ref "Q5") (pin "2") (pinfunction "D_2") (pintype "passive"))
    )
    (net (code "48") (name "Net-(J4-3)") (class "Default")
      (node (ref "J4") (pin "I/O") (pinfunction "3_I/O") (pintype "bidirectional"))
      (node (ref "R34") (pin "2") (pinfunction "2_2") (pintype "passive"))
    )
    (net (code "49") (name "Net-(J5-2)") (class "Default")
      (node (ref "J5") (pin "PWM") (pinfunction "2_PWM") (pintype "bidirectional"))
      (node (ref "LED8") (pin "C") (pinfunction "C_C") (pintype "passive"))
      (node (ref "Q6") (pin "2") (pinfunction "D_2") (pintype "passive"))
    )
    (net (code "50") (name "Net-(J5-3)") (class "Default")
      (node (ref "J5") (pin "I/O") (pinfunction "3_I/O") (pintype "bidirectional"))
      (node (ref "R35") (pin "2") (pinfunction "2_2") (pintype "passive"))
    )
    (net (code "51") (name "Net-(LED2-PadA)") (class "Default")
      (node (ref "LED2") (pin "A") (pinfunction "A_A") (pintype "passive"))
      (node (ref "R25") (pin "1") (pinfunction "1_1") (pintype "passive"))
    )
    (net (code "52") (name "Net-(LED3-PadC)") (class "Default")
      (node (ref "LED3") (pin "C") (pinfunction "C_C") (pintype "passive"))
      (node (ref "RL2") (pin "2") (pinfunction "2_2") (pintype "passive"))
    )
    (net (code "53") (name "Net-(LED4-PadA)") (class "Default")
      (node (ref "LED4") (pin "A") (pinfunction "A_A") (pintype "passive"))
      (node (ref "RL4") (pin "2") (pinfunction "2_2") (pintype "passive"))
    )
    (net (code "54") (name "Net-(LED5-PadA)") (class "Default")
      (node (ref "LED5") (pin "A") (pinfunction "A_A") (pintype "passive"))
      (node (ref "R4") (pin "1") (pinfunction "1_1") (pintype "passive"))
    )
    (net (code "55") (name "Net-(LED6-PadA)") (class "Default")
      (node (ref "LED6") (pin "A") (pinfunction "A_A") (pintype "passive"))
      (node (ref "R5") (pin "1") (pinfunction "1_1") (pintype "passive"))
    )
    (net (code "56") (name "Net-(LED7-PadA)") (class "Default")
      (node (ref "LED7") (pin "A") (pinfunction "A_A") (pintype "passive"))
      (node (ref "R6") (pin "1") (pinfunction "1_1") (pintype "passive"))
    )
    (net (code "57") (name "Net-(LED8-PadA)") (class "Default")
      (node (ref "LED8") (pin "A") (pinfunction "A_A") (pintype "passive"))
      (node (ref "R7") (pin "1") (pinfunction "1_1") (pintype "passive"))
    )
    (net (code "58") (name "Net-(LED9-PadA)") (class "Default")
      (node (ref "LED9") (pin "A") (pinfunction "A_A") (pintype "passive"))
      (node (ref "R12") (pin "1") (pinfunction "1_1") (pintype "passive"))
    )
    (net (code "59") (name "Net-(LED10-PadA)") (class "Default")
      (node (ref "LED10") (pin "A") (pinfunction "A_A") (pintype "passive"))
      (node (ref "RL3") (pin "1") (pinfunction "1_1") (pintype "passive"))
    )
    (net (code "60") (name "Net-(LED11-PadA)") (class "Default")
      (node (ref "LED11") (pin "A") (pinfunction "A_A") (pintype "passive"))
      (node (ref "R14") (pin "1") (pinfunction "1_1") (pintype "passive"))
    )
    (net (code "61") (name "Net-(LED11-PadC)") (class "Default")
      (node (ref "LED11") (pin "C") (pinfunction "C_C") (pintype "passive"))
      (node (ref "U$3") (pin "NET") (pinfunction "NET_NET") (pintype "bidirectional"))
    )
    (net (code "62") (name "Net-(LED12-PadA)") (class "Default")
      (node (ref "LED12") (pin "A") (pinfunction "A_A") (pintype "passive"))
      (node (ref "R39") (pin "1") (pinfunction "1_1") (pintype "passive"))
    )
    (net (code "63") (name "Net-(LED12-PadC)") (class "Default")
      (node (ref "LED12") (pin "C") (pinfunction "C_C") (pintype "passive"))
      (node (ref "U$3") (pin "ALM") (pinfunction "ALM_ALM") (pintype "bidirectional"))
    )
    (net (code "64") (name "Net-(LED13-PadC)") (class "Default")
      (node (ref "LED13") (pin "C") (pinfunction "C_C") (pintype "passive"))
      (node (ref "RL8") (pin "2") (pinfunction "2_2") (pintype "passive"))
    )
    (net (code "65") (name "Net-(LED14-PadC)") (class "Default")
      (node (ref "LED14") (pin "C") (pinfunction "C_C") (pintype "passive"))
      (node (ref "RL9") (pin "2") (pinfunction "2_2") (pintype "passive"))
    )
    (net (code "66") (name "Net-(LED15-PadC)") (class "Default")
      (node (ref "LED15") (pin "C") (pinfunction "C_C") (pintype "passive"))
      (node (ref "RL10") (pin "2") (pinfunction "2_2") (pintype "passive"))
    )
    (net (code "67") (name "Net-(LED16-PadC)") (class "Default")
      (node (ref "LED16") (pin "C") (pinfunction "C_C") (pintype "passive"))
      (node (ref "RL11") (pin "2") (pinfunction "2_2") (pintype "passive"))
    )
    (net (code "68") (name "Net-(LED17-PadC)") (class "Default")
      (node (ref "LED17") (pin "C") (pinfunction "C_C") (pintype "passive"))
      (node (ref "RL12") (pin "2") (pinfunction "2_2") (pintype "passive"))
    )
    (net (code "69") (name "Net-(LED18-PadA)") (class "Default")
      (node (ref "LED18") (pin "A") (pinfunction "A_A") (pintype "passive"))
      (node (ref "RL1") (pin "2") (pinfunction "2_2") (pintype "passive"))
    )
    (net (code "70") (name "Net-(LED19-PadA)") (class "Default")
      (node (ref "LED19") (pin "A") (pinfunction "A_A") (pintype "passive"))
      (node (ref "RL7") (pin "2") (pinfunction "2_2") (pintype "passive"))
    )
    (net (code "71") (name "Net-(R8-Pad2)") (class "Default")
      (node (ref "R8") (pin "2") (pinfunction "2_2") (pintype "passive"))
      (node (ref "U$3") (pin "TX1") (pinfunction "TX1_TX1") (pintype "bidirectional"))
    )
    (net (code "72") (name "Net-(R11-Pad2)") (class "Default")
      (node (ref "R11") (pin "2") (pinfunction "2_2") (pintype "passive"))
      (node (ref "U$3") (pin "RX1") (pinfunction "RX1_RX1") (pintype "bidirectional"))
    )
    (net (code "73") (name "Net-(R24-Pad2)") (class "Default")
      (node (ref "R24") (pin "2") (pinfunction "2_2") (pintype "passive"))
      (node (ref "X4") (pin "3") (pinfunction "3_3") (pintype "passive"))
    )
    (net (code "74") (name "Net-(R31-Pad2)") (class "Default")
      (node (ref "R31") (pin "2") (pinfunction "2_2") (pintype "passive"))
      (node (ref "X4") (pin "2") (pinfunction "2_2") (pintype "passive"))
    )
    (net (code "75") (name "Net-(RGB-J1-2)") (class "Default")
      (node (ref "Q8") (pin "2") (pinfunction "D_2") (pintype "passive"))
      (node (ref "RGB-J1") (pin "R") (pinfunction "2_R") (pintype "bidirectional"))
      (node (ref "RL2") (pin "1") (pinfunction "1_1") (pintype "passive"))
    )
    (net (code "76") (name "Net-(RGB-J1-3)") (class "Default")
      (node (ref "Q9") (pin "2") (pinfunction "D_2") (pintype "passive"))
      (node (ref "RGB-J1") (pin "B") (pinfunction "3_B") (pintype "bidirectional"))
      (node (ref "RL8") (pin "1") (pinfunction "1_1") (pintype "passive"))
    )
    (net (code "77") (name "Net-(RGB-J1-4)") (class "Default")
      (node (ref "Q10") (pin "2") (pinfunction "D_2") (pintype "passive"))
      (node (ref "RGB-J1") (pin "G") (pinfunction "4_G") (pintype "bidirectional"))
      (node (ref "RL9") (pin "1") (pinfunction "1_1") (pintype "passive"))
    )
    (net (code "78") (name "Net-(RGB-J2-2)") (class "Default")
      (node (ref "Q7") (pin "2") (pinfunction "D_2") (pintype "passive"))
      (node (ref "RGB-J2") (pin "R") (pinfunction "2_R") (pintype "bidirectional"))
      (node (ref "RL10") (pin "1") (pinfunction "1_1") (pintype "passive"))
    )
    (net (code "79") (name "Net-(RGB-J2-3)") (class "Default")
      (node (ref "Q11") (pin "2") (pinfunction "D_2") (pintype "passive"))
      (node (ref "RGB-J2") (pin "B") (pinfunction "3_B") (pintype "bidirectional"))
      (node (ref "RL11") (pin "1") (pinfunction "1_1") (pintype "passive"))
    )
    (net (code "80") (name "Net-(RGB-J2-4)") (class "Default")
      (node (ref "Q12") (pin "2") (pinfunction "D_2") (pintype "passive"))
      (node (ref "RGB-J2") (pin "G") (pinfunction "4_G") (pintype "bidirectional"))
      (node (ref "RL12") (pin "1") (pinfunction "1_1") (pintype "passive"))
    )
    (net (code "81") (name "Net-(U$3-RNU)") (class "Default")
      (node (ref "LED9") (pin "C") (pinfunction "C_C") (pintype "passive"))
      (node (ref "U$3") (pin "RUN") (pinfunction "RNU_RUN") (pintype "bidirectional"))
    )
    (net (code "82") (name "Net-(U$4-UCAP)") (class "Default")
      (node (ref "C3") (pin "2") (pinfunction "2_2") (pintype "passive"))
      (node (ref "U$4") (pin "6") (pinfunction "UCAP_6") (pintype "bidirectional"))
    )
    (net (code "83") (name "VUSB") (class "Default")
      (node (ref "C7") (pin "2") (pinfunction "2_2") (pintype "passive"))
      (node (ref "D4") (pin "A") (pinfunction "A_A") (pintype "passive"))
      (node (ref "U$4") (pin "7") (pinfunction "VBUS_7") (pintype "bidirectional"))
      (node (ref "X4") (pin "1") (pinfunction "1_1") (pintype "passive"))
    )
    (net (code "84") (name "unconnected-(CFG-Pad2)") (class "Default")
      (node (ref "CFG") (pin "2") (pinfunction "2_2") (pintype "passive"))
    )
    (net (code "85") (name "unconnected-(CFG-Pad3)") (class "Default")
      (node (ref "CFG") (pin "3") (pinfunction "3_3") (pintype "passive"))
    )
    (net (code "86") (name "unconnected-(Q1-D-Pad4)") (class "Default")
      (node (ref "Q1") (pin "4") (pinfunction "D_4") (pintype "passive"))
    )
    (net (code "87") (name "unconnected-(Q2-D-Pad4)") (class "Default")
      (node (ref "Q2") (pin "4") (pinfunction "D_4") (pintype "passive"))
    )
    (net (code "88") (name "unconnected-(Q4-D-Pad4)") (class "Default")
      (node (ref "Q4") (pin "4") (pinfunction "D_4") (pintype "passive"))
    )
    (net (code "89") (name "unconnected-(Q5-D-Pad4)") (class "Default")
      (node (ref "Q5") (pin "4") (pinfunction "D_4") (pintype "passive"))
    )
    (net (code "90") (name "unconnected-(Q6-D-Pad4)") (class "Default")
      (node (ref "Q6") (pin "4") (pinfunction "D_4") (pintype "passive"))
    )
    (net (code "91") (name "unconnected-(Q7-D-Pad4)") (class "Default")
      (node (ref "Q7") (pin "4") (pinfunction "D_4") (pintype "passive"))
    )
    (net (code "92") (name "unconnected-(Q8-D-Pad4)") (class "Default")
      (node (ref "Q8") (pin "4") (pinfunction "D_4") (pintype "passive"))
    )
    (net (code "93") (name "unconnected-(Q9-D-Pad4)") (class "Default")
      (node (ref "Q9") (pin "4") (pinfunction "D_4") (pintype "passive"))
    )
    (net (code "94") (name "unconnected-(Q10-D-Pad4)") (class "Default")
      (node (ref "Q10") (pin "4") (pinfunction "D_4") (pintype "passive"))
    )
    (net (code "95") (name "unconnected-(Q11-D-Pad4)") (class "Default")
      (node (ref "Q11") (pin "4") (pinfunction "D_4") (pintype "passive"))
    )
    (net (code "96") (name "unconnected-(Q12-D-Pad4)") (class "Default")
      (node (ref "Q12") (pin "4") (pinfunction "D_4") (pintype "passive"))
    )
    (net (code "97") (name "unconnected-(RESET1-Pad1)") (class "Default")
      (node (ref "RESET1") (pin "1") (pinfunction "1_1") (pintype "passive"))
    )
    (net (code "98") (name "unconnected-(RESET1-Pad3)") (class "Default")
      (node (ref "RESET1") (pin "3") (pinfunction "3_3") (pintype "passive"))
    )
    (net (code "99") (name "unconnected-(U$3-PadRST)") (class "Default")
      (node (ref "U$3") (pin "RST") (pinfunction "RST_RST") (pintype "bidirectional"))
    )
    (net (code "100") (name "unconnected-(X4-Pad4)") (class "Default")
      (node (ref "X4") (pin "4") (pinfunction "4_4") (pintype "passive"))
    )
  )
)
